# Singularitron_Enviro-Module_v1.net
KiCad netlist of a schematic drawn in EAGLE
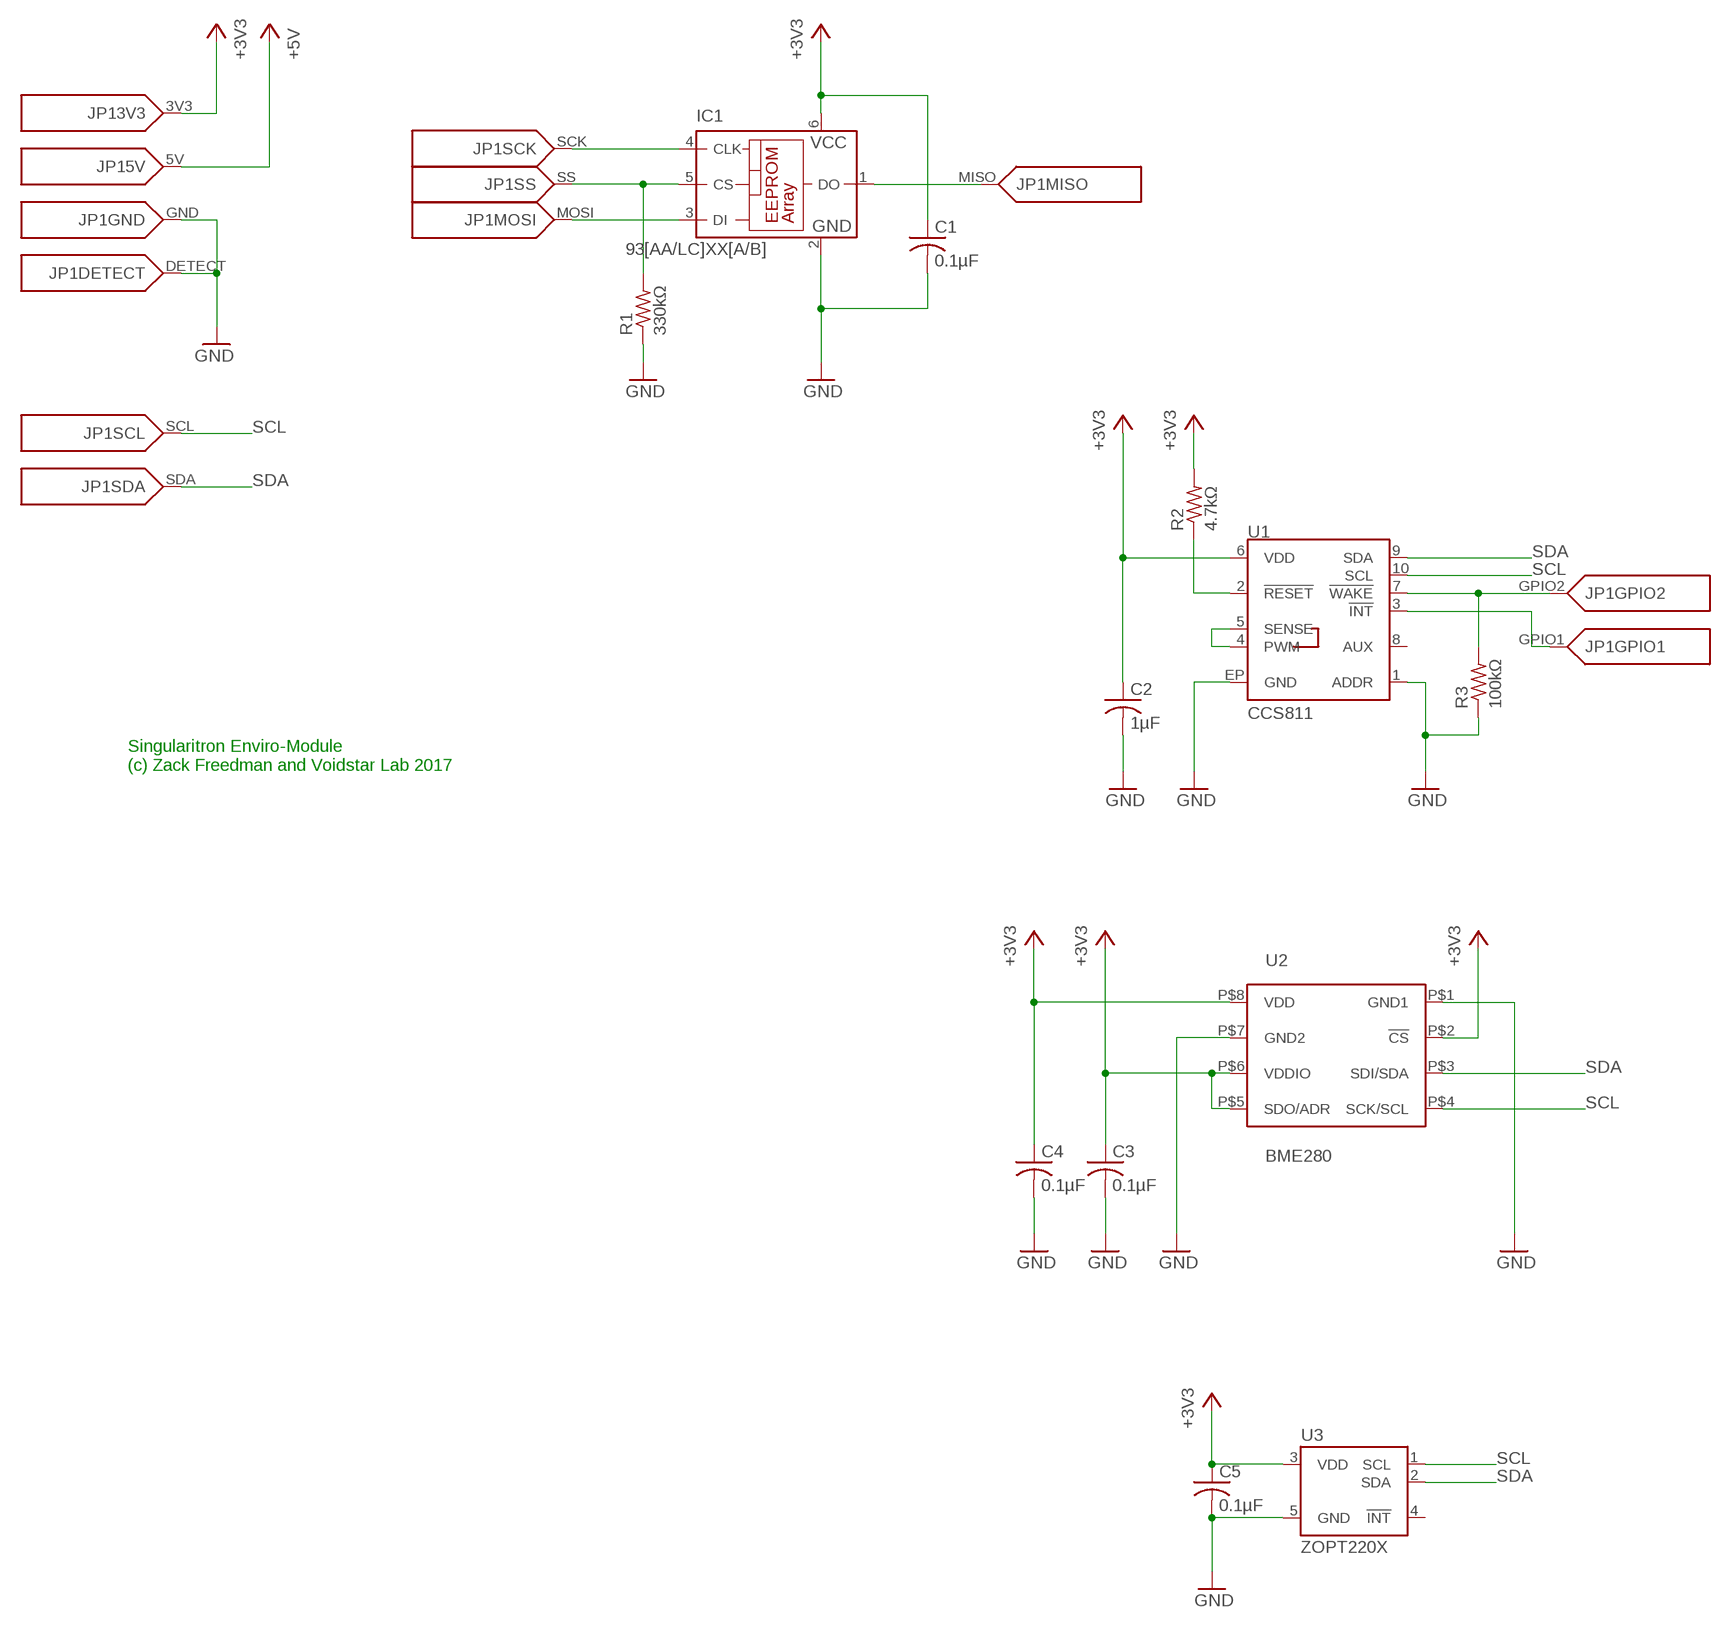
[diagram p0: schematic, sheet 1]

(export (version "E")
  (design (tool "Eeschema 10.0.6"))
  (components
    (comp (ref "C1")
      (value "0.1µF")
      (footprint "eagle-import:C0603")
      (libsource (lib "eagle-import") (part "C-USC0603"))
    )
    (comp (ref "C2")
      (value "1µF")
      (footprint "eagle-import:C0603")
      (libsource (lib "eagle-import") (part "C-USC0603"))
    )
    (comp (ref "C3")
      (value "0.1µF")
      (footprint "eagle-import:C0603")
      (libsource (lib "eagle-import") (part "C-USC0603"))
    )
    (comp (ref "C4")
      (value "0.1µF")
      (footprint "eagle-import:C0603")
      (libsource (lib "eagle-import") (part "C-USC0603"))
    )
    (comp (ref "C5")
      (value "0.1µF")
      (footprint "eagle-import:C0603")
      (libsource (lib "eagle-import") (part "C-USC0603"))
    )
    (comp (ref "IC1")
      (value "93[AA/LC]XX[A/B]")
      (footprint "eagle-import:SOT23-6")
      (fields (field (name "MPN") "93AA76AT-I/OT"))
      (libsource (lib "eagle-import") (part "9376?AAA"))
    )
    (comp (ref "JP1")
      (value "SINGULARITRON_CART_BASE")
      (footprint "eagle-import:SINGULARITRON_CART_BASE")
      (libsource (lib "eagle-import") (part "SINGULARITRON_CART_BASE"))
    )
    (comp (ref "R1")
      (value "330kΩ")
      (footprint "eagle-import:R0603")
      (libsource (lib "eagle-import") (part "R-US_R0603"))
    )
    (comp (ref "R2")
      (value "4.7kΩ")
      (footprint "eagle-import:R0603")
      (libsource (lib "eagle-import") (part "R-US_R0603"))
    )
    (comp (ref "R3")
      (value "100kΩ")
      (footprint "eagle-import:R0603")
      (libsource (lib "eagle-import") (part "R-US_R0603"))
    )
    (comp (ref "U1")
      (value "CCS811")
      (footprint "eagle-import:LGA10")
      (libsource (lib "eagle-import") (part "CCS811"))
    )
    (comp (ref "U2")
      (value "BME280")
      (footprint "eagle-import:BME280_LGA")
      (libsource (lib "eagle-import") (part "BME280"))
    )
    (comp (ref "U3")
      (value "ZOPT220X")
      (footprint "eagle-import:LGA6")
      (libsource (lib "eagle-import") (part "ZOPT220X"))
    )
  )
  (nets
    (net (code "1") (name "+3V3") (class "Default")
      (node (ref "C1") (pin "1") (pinfunction "1_1") (pintype "passive"))
      (node (ref "C2") (pin "1") (pinfunction "1_1") (pintype "passive"))
      (node (ref "C3") (pin "1") (pinfunction "1_1") (pintype "passive"))
      (node (ref "C4") (pin "1") (pinfunction "1_1") (pintype "passive"))
      (node (ref "C5") (pin "1") (pinfunction "1_1") (pintype "passive"))
      (node (ref "IC1") (pin "6") (pinfunction "VCC_6") (pintype "power_in"))
      (node (ref "JP1") (pin "3V3") (pinfunction "P$1_3V3") (pintype "bidirectional"))
      (node (ref "R2") (pin "2") (pinfunction "2_2") (pintype "passive"))
      (node (ref "U1") (pin "6") (pinfunction "VDD_6") (pintype "bidirectional"))
      (node (ref "U2") (pin "P$2") (pinfunction "~{CS}_P$2") (pintype "bidirectional"))
      (node (ref "U2") (pin "P$5") (pinfunction "SDO/ADR_P$5") (pintype "bidirectional"))
      (node (ref "U2") (pin "P$6") (pinfunction "VDDIO_P$6") (pintype "bidirectional"))
      (node (ref "U2") (pin "P$8") (pinfunction "VDD_P$8") (pintype "bidirectional"))
      (node (ref "U3") (pin "3") (pinfunction "VDD_3") (pintype "bidirectional"))
    )
    (net (code "2") (name "+5V") (class "Default")
      (node (ref "JP1") (pin "5V") (pinfunction "P$1_5V") (pintype "bidirectional"))
    )
    (net (code "3") (name "/SCL") (class "Default")
      (node (ref "JP1") (pin "SCL") (pinfunction "P$1_SCL") (pintype "bidirectional"))
      (node (ref "U1") (pin "10") (pinfunction "SCL_10") (pintype "bidirectional"))
      (node (ref "U2") (pin "P$4") (pinfunction "SCK/SCL_P$4") (pintype "bidirectional"))
      (node (ref "U3") (pin "1") (pinfunction "SCL_1") (pintype "bidirectional"))
    )
    (net (code "4") (name "/SDA") (class "Default")
      (node (ref "JP1") (pin "SDA") (pinfunction "P$1_SDA") (pintype "bidirectional"))
      (node (ref "U1") (pin "9") (pinfunction "SDA_9") (pintype "bidirectional"))
      (node (ref "U2") (pin "P$3") (pinfunction "SDI/SDA_P$3") (pintype "bidirectional"))
      (node (ref "U3") (pin "2") (pinfunction "SDA_2") (pintype "bidirectional"))
    )
    (net (code "5") (name "GND") (class "Default")
      (node (ref "C1") (pin "2") (pinfunction "2_2") (pintype "passive"))
      (node (ref "C2") (pin "2") (pinfunction "2_2") (pintype "passive"))
      (node (ref "C3") (pin "2") (pinfunction "2_2") (pintype "passive"))
      (node (ref "C4") (pin "2") (pinfunction "2_2") (pintype "passive"))
      (node (ref "C5") (pin "2") (pinfunction "2_2") (pintype "passive"))
      (node (ref "IC1") (pin "2") (pinfunction "GND_2") (pintype "power_in"))
      (node (ref "JP1") (pin "DETECT") (pinfunction "P$1_DETECT") (pintype "bidirectional"))
      (node (ref "JP1") (pin "GND") (pinfunction "P$1_GND") (pintype "bidirectional"))
      (node (ref "R1") (pin "1") (pinfunction "1_1") (pintype "passive"))
      (node (ref "R3") (pin "1") (pinfunction "1_1") (pintype "passive"))
      (node (ref "U1") (pin "1") (pinfunction "ADDR_1") (pintype "bidirectional"))
      (node (ref "U1") (pin "EP") (pinfunction "GND_EP") (pintype "bidirectional"))
      (node (ref "U2") (pin "P$1") (pinfunction "GND1_P$1") (pintype "bidirectional"))
      (node (ref "U2") (pin "P$7") (pinfunction "GND2_P$7") (pintype "bidirectional"))
      (node (ref "U3") (pin "5") (pinfunction "GND_5") (pintype "bidirectional"))
    )
    (net (code "6") (name "Net-(IC1-CLK)") (class "Default")
      (node (ref "IC1") (pin "4") (pinfunction "CLK_4") (pintype "input"))
      (node (ref "JP1") (pin "SCK") (pinfunction "P$1_SCK") (pintype "bidirectional"))
    )
    (net (code "7") (name "Net-(IC1-CS)") (class "Default")
      (node (ref "IC1") (pin "5") (pinfunction "CS_5") (pintype "input"))
      (node (ref "JP1") (pin "SS") (pinfunction "P$1_SS") (pintype "bidirectional"))
      (node (ref "R1") (pin "2") (pinfunction "2_2") (pintype "passive"))
    )
    (net (code "8") (name "Net-(IC1-DI)") (class "Default")
      (node (ref "IC1") (pin "3") (pinfunction "DI_3") (pintype "input"))
      (node (ref "JP1") (pin "MOSI") (pinfunction "P$1_MOSI") (pintype "bidirectional"))
    )
    (net (code "9") (name "Net-(IC1-DO)") (class "Default")
      (node (ref "IC1") (pin "1") (pinfunction "DO_1") (pintype "tri_state"))
      (node (ref "JP1") (pin "MISO") (pinfunction "P$1_MISO") (pintype "bidirectional"))
    )
    (net (code "10") (name "Net-(JP1E-P$1)") (class "Default")
      (node (ref "JP1") (pin "GPIO1") (pinfunction "P$1_GPIO1") (pintype "bidirectional"))
      (node (ref "U1") (pin "3") (pinfunction "~{INT}_3") (pintype "bidirectional"))
    )
    (net (code "11") (name "Net-(JP1F-P$1)") (class "Default")
      (node (ref "JP1") (pin "GPIO2") (pinfunction "P$1_GPIO2") (pintype "bidirectional"))
      (node (ref "R3") (pin "2") (pinfunction "2_2") (pintype "passive"))
      (node (ref "U1") (pin "7") (pinfunction "~{WAKE}_7") (pintype "bidirectional"))
    )
    (net (code "12") (name "Net-(U1-PWM)") (class "Default")
      (node (ref "U1") (pin "4") (pinfunction "PWM_4") (pintype "bidirectional"))
      (node (ref "U1") (pin "5") (pinfunction "SENSE_5") (pintype "bidirectional"))
    )
    (net (code "13") (name "Net-(U1-~{RESET})") (class "Default")
      (node (ref "R2") (pin "1") (pinfunction "1_1") (pintype "passive"))
      (node (ref "U1") (pin "2") (pinfunction "~{RESET}_2") (pintype "bidirectional"))
    )
    (net (code "14") (name "unconnected-(U1-AUX-Pad8)") (class "Default")
      (node (ref "U1") (pin "8") (pinfunction "AUX_8") (pintype "bidirectional"))
    )
    (net (code "15") (name "unconnected-(U3-~{INT}-Pad4)") (class "Default")
      (node (ref "U3") (pin "4") (pinfunction "~{INT}_4") (pintype "bidirectional"))
    )
  )
)
